# E6_funk_v2.net
KiCad netlist of a schematic drawn in EAGLE
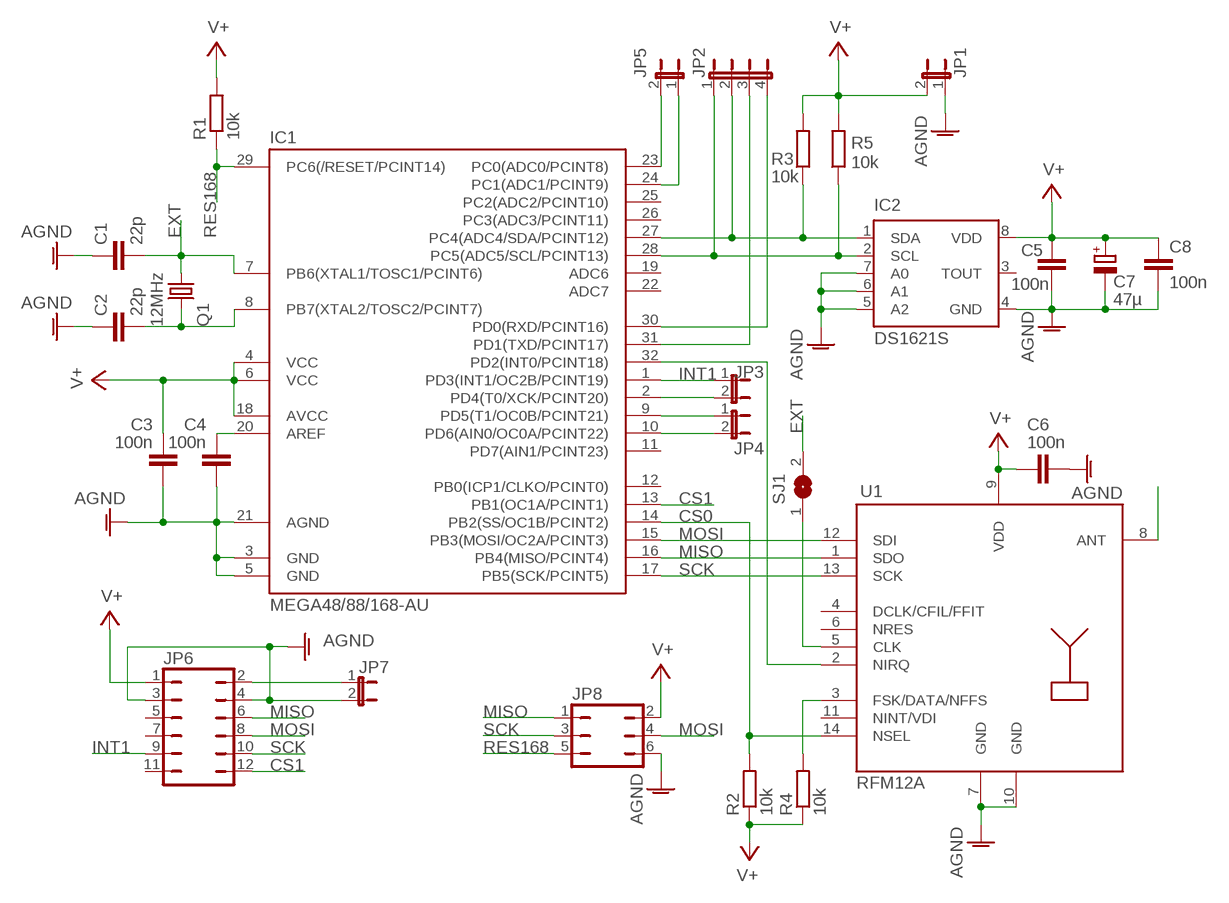
[diagram p0: schematic, sheet 1]

(export (version "E")
  (design (tool "Eeschema 10.0.6"))
  (components
    (comp (ref "C1")
      (value "22p")
      (footprint "eagle-import:C0805K")
      (libsource (lib "eagle-import") (part "C-EUC0805K"))
    )
    (comp (ref "C2")
      (value "22p")
      (footprint "eagle-import:C0805K")
      (libsource (lib "eagle-import") (part "C-EUC0805K"))
    )
    (comp (ref "C3")
      (value "100n")
      (footprint "eagle-import:C0805K")
      (libsource (lib "eagle-import") (part "C-EUC0805K"))
    )
    (comp (ref "C4")
      (value "100n")
      (footprint "eagle-import:C0805K")
      (libsource (lib "eagle-import") (part "C-EUC0805K"))
    )
    (comp (ref "C5")
      (value "100n")
      (footprint "eagle-import:C0805K")
      (libsource (lib "eagle-import") (part "C-EUC0805K"))
    )
    (comp (ref "C6")
      (value "100n")
      (footprint "eagle-import:C0805K")
      (libsource (lib "eagle-import") (part "C-EUC0805K"))
    )
    (comp (ref "C7")
      (value "47µ")
      (footprint "eagle-import:SMC_D")
      (libsource (lib "eagle-import") (part "CPOL-EUSMCD"))
    )
    (comp (ref "C8")
      (value "100n")
      (footprint "eagle-import:C0805K")
      (libsource (lib "eagle-import") (part "C-EUC0805K"))
    )
    (comp (ref "IC1")
      (value "MEGA48/88/168-AU")
      (footprint "eagle-import:TQFP32-08")
      (libsource (lib "eagle-import") (part "MEGA48/88/168-AU"))
    )
    (comp (ref "IC2")
      (value "DS1621S")
      (footprint "eagle-import:SO08")
      (libsource (lib "eagle-import") (part "DS1621S"))
    )
    (comp (ref "JP1")
      (value "JP1E")
      (footprint "eagle-import:JP1")
      (libsource (lib "eagle-import") (part "JP1E"))
    )
    (comp (ref "JP2")
      (value "JP4E")
      (footprint "eagle-import:JP4")
      (libsource (lib "eagle-import") (part "JP4E"))
    )
    (comp (ref "JP3")
      (value "JP1E")
      (footprint "eagle-import:JP1")
      (libsource (lib "eagle-import") (part "JP1E"))
    )
    (comp (ref "JP4")
      (value "JP1E")
      (footprint "eagle-import:JP1")
      (libsource (lib "eagle-import") (part "JP1E"))
    )
    (comp (ref "JP5")
      (value "JP1E")
      (footprint "eagle-import:JP1")
      (libsource (lib "eagle-import") (part "JP1E"))
    )
    (comp (ref "JP6")
      (value "JP6Q")
      (footprint "eagle-import:JP6Q")
      (libsource (lib "eagle-import") (part "JP6Q"))
    )
    (comp (ref "JP7")
      (value "JP1E")
      (footprint "eagle-import:JP1")
      (libsource (lib "eagle-import") (part "JP1E"))
    )
    (comp (ref "JP8")
      (value "JP3Q")
      (footprint "eagle-import:JP3Q")
      (libsource (lib "eagle-import") (part "JP3Q"))
    )
    (comp (ref "Q1")
      (value "12MHz")
      (footprint "eagle-import:CTS406")
      (libsource (lib "eagle-import") (part "CRYSTALCTS406"))
    )
    (comp (ref "R1")
      (value "10k")
      (footprint "eagle-import:R0805")
      (libsource (lib "eagle-import") (part "R-EU_R0805"))
    )
    (comp (ref "R2")
      (value "10k")
      (footprint "eagle-import:R0805")
      (libsource (lib "eagle-import") (part "R-EU_R0805"))
    )
    (comp (ref "R3")
      (value "10k")
      (footprint "eagle-import:R0805")
      (libsource (lib "eagle-import") (part "R-EU_R0805"))
    )
    (comp (ref "R4")
      (value "10k")
      (footprint "eagle-import:R0805")
      (libsource (lib "eagle-import") (part "R-EU_R0805"))
    )
    (comp (ref "R5")
      (value "10k")
      (footprint "eagle-import:R0805")
      (libsource (lib "eagle-import") (part "R-EU_R0805"))
    )
    (comp (ref "SJ1") (value "SJ") (footprint "eagle-import:SJ") (libsource (lib "eagle-import") (part "SJ")))
    (comp (ref "U1")
      (value "RFM12A")
      (footprint "eagle-import:RFM1")
      (libsource (lib "eagle-import") (part "RFM12A"))
    )
  )
  (nets
    (net (code "1") (name "/CS0") (class "Default")
      (node (ref "IC1") (pin "14") (pinfunction "PB2(SS/OC1B/PCINT2)_14") (pintype "bidirectional"))
      (node (ref "R2") (pin "2") (pinfunction "2_2") (pintype "passive"))
      (node (ref "U1") (pin "14") (pinfunction "NSEL_14") (pintype "bidirectional"))
    )
    (net (code "2") (name "/CS1") (class "Default")
      (node (ref "IC1") (pin "13") (pinfunction "PB1(OC1A/PCINT1)_13") (pintype "bidirectional"))
      (node (ref "JP6") (pin "12") (pinfunction "12_12") (pintype "passive"))
    )
    (net (code "3") (name "/EXT") (class "Default")
      (node (ref "C1") (pin "1") (pinfunction "1_1") (pintype "passive"))
      (node (ref "IC1") (pin "7") (pinfunction "PB6(XTAL1/TOSC1/PCINT6)_7") (pintype "bidirectional"))
      (node (ref "Q1") (pin "1") (pinfunction "1_1") (pintype "passive"))
      (node (ref "SJ1") (pin "2") (pinfunction "2_2") (pintype "passive"))
    )
    (net (code "4") (name "/INT1") (class "Default")
      (node (ref "IC1") (pin "1") (pinfunction "PD3(INT1/OC2B/PCINT19)_1") (pintype "bidirectional"))
      (node (ref "JP3") (pin "1") (pinfunction "1_1") (pintype "passive"))
      (node (ref "JP6") (pin "9") (pinfunction "9_9") (pintype "passive"))
    )
    (net (code "5") (name "/MISO") (class "Default")
      (node (ref "IC1") (pin "16") (pinfunction "PB4(MISO/PCINT4)_16") (pintype "bidirectional"))
      (node (ref "JP6") (pin "6") (pinfunction "6_6") (pintype "passive"))
      (node (ref "JP8") (pin "1") (pinfunction "1_1") (pintype "passive"))
      (node (ref "U1") (pin "1") (pinfunction "SDO_1") (pintype "bidirectional"))
    )
    (net (code "6") (name "/MOSI") (class "Default")
      (node (ref "IC1") (pin "15") (pinfunction "PB3(MOSI/OC2A/PCINT3)_15") (pintype "bidirectional"))
      (node (ref "JP6") (pin "8") (pinfunction "8_8") (pintype "passive"))
      (node (ref "JP8") (pin "4") (pinfunction "4_4") (pintype "passive"))
      (node (ref "U1") (pin "12") (pinfunction "SDI_12") (pintype "bidirectional"))
    )
    (net (code "7") (name "/RES168") (class "Default")
      (node (ref "IC1") (pin "29") (pinfunction "PC6(/RESET/PCINT14)_29") (pintype "bidirectional"))
      (node (ref "JP8") (pin "5") (pinfunction "5_5") (pintype "passive"))
      (node (ref "R1") (pin "1") (pinfunction "1_1") (pintype "passive"))
    )
    (net (code "8") (name "/SCK") (class "Default")
      (node (ref "IC1") (pin "17") (pinfunction "PB5(SCK/PCINT5)_17") (pintype "bidirectional"))
      (node (ref "JP6") (pin "10") (pinfunction "10_10") (pintype "passive"))
      (node (ref "JP8") (pin "3") (pinfunction "3_3") (pintype "passive"))
      (node (ref "U1") (pin "13") (pinfunction "SCK_13") (pintype "bidirectional"))
    )
    (net (code "9") (name "AGND") (class "Default")
      (node (ref "C1") (pin "2") (pinfunction "2_2") (pintype "passive"))
      (node (ref "C2") (pin "2") (pinfunction "2_2") (pintype "passive"))
      (node (ref "C3") (pin "1") (pinfunction "1_1") (pintype "passive"))
      (node (ref "C4") (pin "1") (pinfunction "1_1") (pintype "passive"))
      (node (ref "C5") (pin "2") (pinfunction "2_2") (pintype "passive"))
      (node (ref "C6") (pin "1") (pinfunction "1_1") (pintype "passive"))
      (node (ref "C7") (pin "-") (pinfunction "-_-") (pintype "passive"))
      (node (ref "C8") (pin "2") (pinfunction "2_2") (pintype "passive"))
      (node (ref "IC1") (pin "21") (pinfunction "AGND_21") (pintype "power_in"))
      (node (ref "IC1") (pin "3") (pinfunction "GND_3") (pintype "power_in"))
      (node (ref "IC1") (pin "5") (pinfunction "GND_5") (pintype "power_in"))
      (node (ref "IC2") (pin "4") (pinfunction "GND_4") (pintype "power_in"))
      (node (ref "IC2") (pin "5") (pinfunction "A2_5") (pintype "input"))
      (node (ref "IC2") (pin "6") (pinfunction "A1_6") (pintype "input"))
      (node (ref "IC2") (pin "7") (pinfunction "A0_7") (pintype "input"))
      (node (ref "JP1") (pin "1") (pinfunction "1_1") (pintype "passive"))
      (node (ref "JP6") (pin "3") (pinfunction "3_3") (pintype "passive"))
      (node (ref "JP6") (pin "4") (pinfunction "4_4") (pintype "passive"))
      (node (ref "JP7") (pin "2") (pinfunction "2_2") (pintype "passive"))
      (node (ref "JP8") (pin "6") (pinfunction "6_6") (pintype "passive"))
      (node (ref "U1") (pin "10") (pinfunction "GND_10") (pintype "power_in"))
      (node (ref "U1") (pin "7") (pinfunction "GND_7") (pintype "power_in"))
    )
    (net (code "10") (name "Net-(IC1-AREF)") (class "Default")
      (node (ref "C4") (pin "2") (pinfunction "2_2") (pintype "passive"))
      (node (ref "IC1") (pin "20") (pinfunction "AREF_20") (pintype "passive"))
    )
    (net (code "11") (name "Net-(IC1-PB7(XTAL2{slash}TOSC2{slash}PCINT7))") (class "Default")
      (node (ref "C2") (pin "1") (pinfunction "1_1") (pintype "passive"))
      (node (ref "IC1") (pin "8") (pinfunction "PB7(XTAL2/TOSC2/PCINT7)_8") (pintype "bidirectional"))
      (node (ref "Q1") (pin "3") (pinfunction "2_3") (pintype "passive"))
    )
    (net (code "12") (name "Net-(IC1-PC0(ADC0{slash}PCINT8))") (class "Default")
      (node (ref "IC1") (pin "23") (pinfunction "PC0(ADC0/PCINT8)_23") (pintype "bidirectional"))
      (node (ref "JP5") (pin "2") (pinfunction "2_2") (pintype "passive"))
    )
    (net (code "13") (name "Net-(IC1-PC1(ADC1{slash}PCINT9))") (class "Default")
      (node (ref "IC1") (pin "24") (pinfunction "PC1(ADC1/PCINT9)_24") (pintype "bidirectional"))
      (node (ref "JP5") (pin "1") (pinfunction "1_1") (pintype "passive"))
    )
    (net (code "14") (name "Net-(IC1-PC4(ADC4{slash}SDA{slash}PCINT12))") (class "Default")
      (node (ref "IC1") (pin "27") (pinfunction "PC4(ADC4/SDA/PCINT12)_27") (pintype "bidirectional"))
      (node (ref "IC2") (pin "1") (pinfunction "SDA_1") (pintype "bidirectional"))
      (node (ref "JP2") (pin "2") (pinfunction "2_2") (pintype "passive"))
      (node (ref "R3") (pin "1") (pinfunction "1_1") (pintype "passive"))
    )
    (net (code "15") (name "Net-(IC1-PC5(ADC5{slash}SCL{slash}PCINT13))") (class "Default")
      (node (ref "IC1") (pin "28") (pinfunction "PC5(ADC5/SCL/PCINT13)_28") (pintype "bidirectional"))
      (node (ref "IC2") (pin "2") (pinfunction "SCL_2") (pintype "input"))
      (node (ref "JP2") (pin "1") (pinfunction "1_1") (pintype "passive"))
      (node (ref "R5") (pin "1") (pinfunction "1_1") (pintype "passive"))
    )
    (net (code "16") (name "Net-(IC1-PD0(RXD{slash}PCINT16))") (class "Default")
      (node (ref "IC1") (pin "30") (pinfunction "PD0(RXD/PCINT16)_30") (pintype "bidirectional"))
      (node (ref "JP2") (pin "4") (pinfunction "4_4") (pintype "passive"))
    )
    (net (code "17") (name "Net-(IC1-PD1(TXD{slash}PCINT17))") (class "Default")
      (node (ref "IC1") (pin "31") (pinfunction "PD1(TXD/PCINT17)_31") (pintype "bidirectional"))
      (node (ref "JP2") (pin "3") (pinfunction "3_3") (pintype "passive"))
    )
    (net (code "18") (name "Net-(IC1-PD2(INT0{slash}PCINT18))") (class "Default")
      (node (ref "IC1") (pin "32") (pinfunction "PD2(INT0/PCINT18)_32") (pintype "bidirectional"))
      (node (ref "U1") (pin "2") (pinfunction "NIRQ_2") (pintype "bidirectional"))
    )
    (net (code "19") (name "Net-(IC1-PD4(T0{slash}XCK{slash}PCINT20))") (class "Default")
      (node (ref "IC1") (pin "2") (pinfunction "PD4(T0/XCK/PCINT20)_2") (pintype "bidirectional"))
      (node (ref "JP3") (pin "2") (pinfunction "2_2") (pintype "passive"))
    )
    (net (code "20") (name "Net-(IC1-PD5(T1{slash}OC0B{slash}PCINT21))") (class "Default")
      (node (ref "IC1") (pin "9") (pinfunction "PD5(T1/OC0B/PCINT21)_9") (pintype "bidirectional"))
      (node (ref "JP4") (pin "1") (pinfunction "1_1") (pintype "passive"))
    )
    (net (code "21") (name "Net-(IC1-PD6(AIN0{slash}OC0A{slash}PCINT22))") (class "Default")
      (node (ref "IC1") (pin "10") (pinfunction "PD6(AIN0/OC0A/PCINT22)_10") (pintype "bidirectional"))
      (node (ref "JP4") (pin "2") (pinfunction "2_2") (pintype "passive"))
    )
    (net (code "22") (name "Net-(JP6-Pad2)") (class "Default")
      (node (ref "JP6") (pin "2") (pinfunction "2_2") (pintype "passive"))
      (node (ref "JP7") (pin "1") (pinfunction "1_1") (pintype "passive"))
    )
    (net (code "23") (name "Net-(U1-CLK)") (class "Default")
      (node (ref "SJ1") (pin "1") (pinfunction "1_1") (pintype "passive"))
      (node (ref "U1") (pin "5") (pinfunction "CLK_5") (pintype "bidirectional"))
    )
    (net (code "24") (name "Net-(U1-FSK{slash}DATA{slash}NFFS)") (class "Default")
      (node (ref "R4") (pin "2") (pinfunction "2_2") (pintype "passive"))
      (node (ref "U1") (pin "3") (pinfunction "FSK/DATA/NFFS_3") (pintype "bidirectional"))
    )
    (net (code "25") (name "V+") (class "Default")
      (node (ref "C3") (pin "2") (pinfunction "2_2") (pintype "passive"))
      (node (ref "C5") (pin "1") (pinfunction "1_1") (pintype "passive"))
      (node (ref "C6") (pin "2") (pinfunction "2_2") (pintype "passive"))
      (node (ref "C7") (pin "+") (pinfunction "+_+") (pintype "passive"))
      (node (ref "C8") (pin "1") (pinfunction "1_1") (pintype "passive"))
      (node (ref "IC1") (pin "18") (pinfunction "AVCC_18") (pintype "passive"))
      (node (ref "IC1") (pin "4") (pinfunction "VCC_4") (pintype "power_in"))
      (node (ref "IC1") (pin "6") (pinfunction "VCC_6") (pintype "power_in"))
      (node (ref "IC2") (pin "8") (pinfunction "VDD_8") (pintype "power_in"))
      (node (ref "JP1") (pin "2") (pinfunction "2_2") (pintype "passive"))
      (node (ref "JP6") (pin "1") (pinfunction "1_1") (pintype "passive"))
      (node (ref "JP8") (pin "2") (pinfunction "2_2") (pintype "passive"))
      (node (ref "R1") (pin "2") (pinfunction "2_2") (pintype "passive"))
      (node (ref "R2") (pin "1") (pinfunction "1_1") (pintype "passive"))
      (node (ref "R3") (pin "2") (pinfunction "2_2") (pintype "passive"))
      (node (ref "R4") (pin "1") (pinfunction "1_1") (pintype "passive"))
      (node (ref "R5") (pin "2") (pinfunction "2_2") (pintype "passive"))
      (node (ref "U1") (pin "9") (pinfunction "VDD_9") (pintype "power_in"))
    )
    (net (code "26") (name "unconnected-(IC1-ADC6-Pad19)") (class "Default")
      (node (ref "IC1") (pin "19") (pinfunction "ADC6_19") (pintype "passive"))
    )
    (net (code "27") (name "unconnected-(IC1-ADC7-Pad22)") (class "Default")
      (node (ref "IC1") (pin "22") (pinfunction "ADC7_22") (pintype "passive"))
    )
    (net (code "28") (name "unconnected-(IC1-PB0(ICP1{slash}CLKO{slash}PCINT0)-Pad12)") (class "Default")
      (node (ref "IC1") (pin "12") (pinfunction "PB0(ICP1/CLKO/PCINT0)_12") (pintype "bidirectional"))
    )
    (net (code "29") (name "unconnected-(IC1-PC2(ADC2{slash}PCINT10)-Pad25)") (class "Default")
      (node (ref "IC1") (pin "25") (pinfunction "PC2(ADC2/PCINT10)_25") (pintype "bidirectional"))
    )
    (net (code "30") (name "unconnected-(IC1-PC3(ADC3{slash}PCINT11)-Pad26)") (class "Default")
      (node (ref "IC1") (pin "26") (pinfunction "PC3(ADC3/PCINT11)_26") (pintype "bidirectional"))
    )
    (net (code "31") (name "unconnected-(IC1-PD7(AIN1{slash}PCINT23)-Pad11)") (class "Default")
      (node (ref "IC1") (pin "11") (pinfunction "PD7(AIN1/PCINT23)_11") (pintype "bidirectional"))
    )
    (net (code "32") (name "unconnected-(IC2-TOUT-Pad3)") (class "Default")
      (node (ref "IC2") (pin "3") (pinfunction "TOUT_3") (pintype "output"))
    )
    (net (code "33") (name "unconnected-(JP6-Pad5)") (class "Default")
      (node (ref "JP6") (pin "5") (pinfunction "5_5") (pintype "passive"))
    )
    (net (code "34") (name "unconnected-(JP6-Pad7)") (class "Default")
      (node (ref "JP6") (pin "7") (pinfunction "7_7") (pintype "passive"))
    )
    (net (code "35") (name "unconnected-(JP6-Pad11)") (class "Default")
      (node (ref "JP6") (pin "11") (pinfunction "11_11") (pintype "passive"))
    )
    (net (code "36") (name "unconnected-(U1-ANT-Pad8)") (class "Default")
      (node (ref "U1") (pin "8") (pinfunction "ANT_8") (pintype "output"))
    )
    (net (code "37") (name "unconnected-(U1-DCLK{slash}CFIL{slash}FFIT-Pad4)") (class "Default")
      (node (ref "U1") (pin "4") (pinfunction "DCLK/CFIL/FFIT_4") (pintype "bidirectional"))
    )
    (net (code "38") (name "unconnected-(U1-NINT{slash}VDI-Pad11)") (class "Default")
      (node (ref "U1") (pin "11") (pinfunction "NINT/VDI_11") (pintype "bidirectional"))
    )
    (net (code "39") (name "unconnected-(U1-NRES-Pad6)") (class "Default")
      (node (ref "U1") (pin "6") (pinfunction "NRES_6") (pintype "bidirectional"))
    )
  )
)
